# DC-DC.net
KiCad netlist of a schematic drawn in Altium Designer
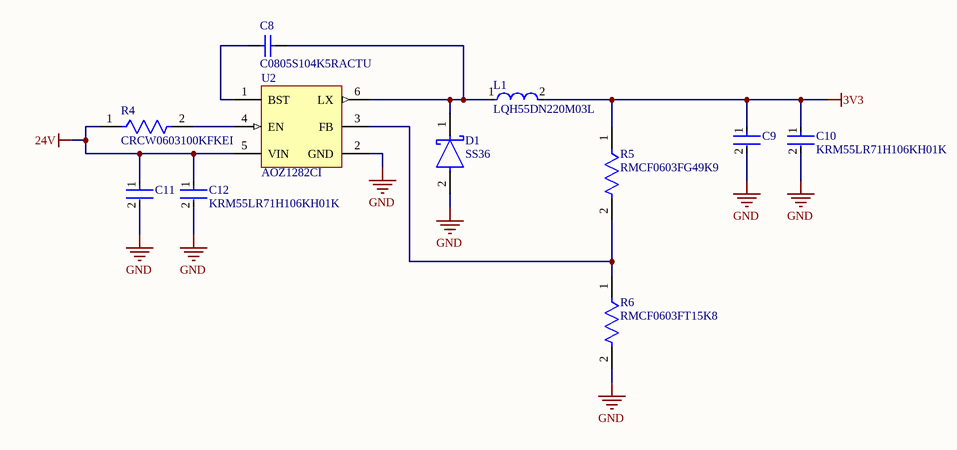
[diagram p0: DC-DC.SchDoc]

(export (version "E")
  (design (tool "Eeschema 10.0.6"))
  (components
    (comp (ref "C8")
      (value "C0805S104K5RACTU")
      (footprint "CAPC2013X145X50NL20T25")
      (description "100 nF 50 VDC X7R 10 % 0805")
      (fields (field (name "MANUFACTURER") "Kemet"))
      (libsource (lib "Altium Content Vault") (part "CAP"))
    )
    (comp (ref "C9")
      (value "KRM55LR71H106KH01K")
      (footprint "FP-KRM55L-6_1_5_3_3_1_2-C-MFG")
      (description "Cap Ceramic Multilayer 10uF 50V ±10% 2220 Emboss T/R")
      (libsource (lib "Altium Content Vault") (part "02cd4be3c70576c341d710602a673aa"))
    )
    (comp (ref "C10")
      (value "KRM55LR71H106KH01K")
      (footprint "FP-KRM55L-6_1_5_3_3_1_2-C-MFG")
      (description "Cap Ceramic Multilayer 10uF 50V ±10% 2220 Emboss T/R")
      (libsource (lib "Altium Content Vault") (part "02cd4be3c70576c341d710602a673aa"))
    )
    (comp (ref "C11")
      (value "KRM55LR71H106KH01K")
      (footprint "FP-KRM55L-6_1_5_3_3_1_2-C-MFG")
      (description "Cap Ceramic Multilayer 10uF 50V ±10% 2220 Emboss T/R")
      (libsource (lib "Altium Content Vault") (part "02cd4be3c70576c341d710602a673aa"))
    )
    (comp (ref "C12")
      (value "KRM55LR71H106KH01K")
      (footprint "FP-KRM55L-6_1_5_3_3_1_2-C-MFG")
      (description "Cap Ceramic Multilayer 10uF 50V ±10% 2220 Emboss T/R")
      (libsource (lib "Altium Content Vault") (part "02cd4be3c70576c341d710602a673aa"))
    )
    (comp (ref "D1")
      (value "SS36")
      (footprint "FP-403AG-MFG")
      (description "DIODE SCHOTTKY 60V 3A SMC")
      (fields
        (field (name "MANUFACTURER") "ON Semiconductor")
        (field (name "OCTOPART") "https://octopart.com/ss36-on+semiconductor-84331627")
      )
      (libsource (lib "Altium Content Vault") (part "1d6ec82d83fb6aee721767c19dac4b9"))
    )
    (comp (ref "L1")
      (value "LQH55DN220M03L")
      (footprint "FP-LQH55DN_03-MFG")
      (description "Wire Wound Ferrite Inductor for Power Lines 22μH ±20% 0.266Ω  1.2A 2220")
      (fields (field (name "TOLERANCE") "20%"))
      (libsource (lib "Altium Content Vault") (part "725321dda6339637d4d059423bc1c3c"))
    )
    (comp (ref "R4")
      (value "CRCW0603100KFKEI")
      (footprint "FP-CRCW0603-e3-MFG")
      (description "RES Thick Film, 100kΩ, 1%, 0.1W, 100ppm/°C, 0603")
      (fields (field (name "TOLERANCE") "1%"))
      (libsource (lib "Altium Content Vault") (part "1029c3af85768c4190bb7ad29bc67b5"))
    )
    (comp (ref "R5")
      (value "RMCF0603FG49K9")
      (footprint "FP-RMCF0603-MFG")
      (description "49.9kΩ ±1% 0.1W 0603 Thick Film Chip Resistor AEC-Q200 compliant")
      (fields (field (name "TOLERANCE") "1%"))
      (libsource (lib "Altium Content Vault") (part "1029c3af85768c4190bb7ad29bc67b5"))
    )
    (comp (ref "R6")
      (value "RMCF0603FT15K8")
      (footprint "FP-RMCF0603-IPC_B")
      (description "15.8kΩ ±1% 0.1W 0603 Thick Film Chip Resistor AEC-Q200 compliant")
      (fields (field (name "TOLERANCE") "1%"))
      (libsource (lib "Altium Content Vault") (part "1029c3af85768c4190bb7ad29bc67b5"))
    )
    (comp (ref "U2")
      (value "AOZ1282CI")
      (footprint "AO-SOT23-6L-6_V")
      (fields (field (name "MANUFACTURER") "Alpha and Omega"))
      (libsource (lib "Altium Content Vault") (part "AO-AOZ1282CI-SOT23-6L-6"))
    )
  )
  (nets
    (net (code "1") (name "3V3") (class "Default")
      (node (ref "C10") (pin "1") (pinfunction "1_1") (pintype "passive"))
      (node (ref "C9") (pin "1") (pinfunction "1_1") (pintype "passive"))
      (node (ref "L1") (pin "2") (pinfunction "2_2") (pintype "passive"))
      (node (ref "R5") (pin "1") (pinfunction "1_1") (pintype "passive"))
    )
    (net (code "2") (name "24V") (class "Default")
      (node (ref "C11") (pin "1") (pinfunction "1_1") (pintype "passive"))
      (node (ref "C12") (pin "1") (pinfunction "1_1") (pintype "passive"))
      (node (ref "R4") (pin "1") (pinfunction "1_1") (pintype "passive"))
      (node (ref "U2") (pin "5") (pinfunction "VIN_5") (pintype "power_in"))
    )
    (net (code "3") (name "GND") (class "Default")
      (node (ref "C10") (pin "2") (pinfunction "2_2") (pintype "passive"))
      (node (ref "C11") (pin "2") (pinfunction "2_2") (pintype "passive"))
      (node (ref "C12") (pin "2") (pinfunction "2_2") (pintype "passive"))
      (node (ref "C9") (pin "2") (pinfunction "2_2") (pintype "passive"))
      (node (ref "D1") (pin "2") (pinfunction "A_2") (pintype "passive"))
      (node (ref "R6") (pin "2") (pinfunction "2_2") (pintype "passive"))
      (node (ref "U2") (pin "2") (pinfunction "GND_2") (pintype "power_in"))
    )
    (net (code "4") (name "Net-(D1-C)") (class "Default")
      (node (ref "C8") (pin "2") (pinfunction "2_2") (pintype "passive"))
      (node (ref "D1") (pin "1") (pinfunction "C_1") (pintype "passive"))
      (node (ref "L1") (pin "1") (pinfunction "1_1") (pintype "passive"))
      (node (ref "U2") (pin "6") (pinfunction "LX_6") (pintype "output"))
    )
    (net (code "5") (name "Net-(U2-BST)") (class "Default")
      (node (ref "C8") (pin "1") (pinfunction "1_1") (pintype "passive"))
      (node (ref "U2") (pin "1") (pinfunction "BST_1") (pintype "power_in"))
    )
    (net (code "6") (name "Net-(U2-EN)") (class "Default")
      (node (ref "R4") (pin "2") (pinfunction "2_2") (pintype "passive"))
      (node (ref "U2") (pin "4") (pinfunction "EN_4") (pintype "input"))
    )
    (net (code "7") (name "Net-(U2-FB)") (class "Default")
      (node (ref "R5") (pin "2") (pinfunction "2_2") (pintype "passive"))
      (node (ref "R6") (pin "1") (pinfunction "1_1") (pintype "passive"))
      (node (ref "U2") (pin "3") (pinfunction "FB_3") (pintype "passive"))
    )
  )
)
